# Makita_PSU.net
KiCad netlist of a schematic drawn in EAGLE
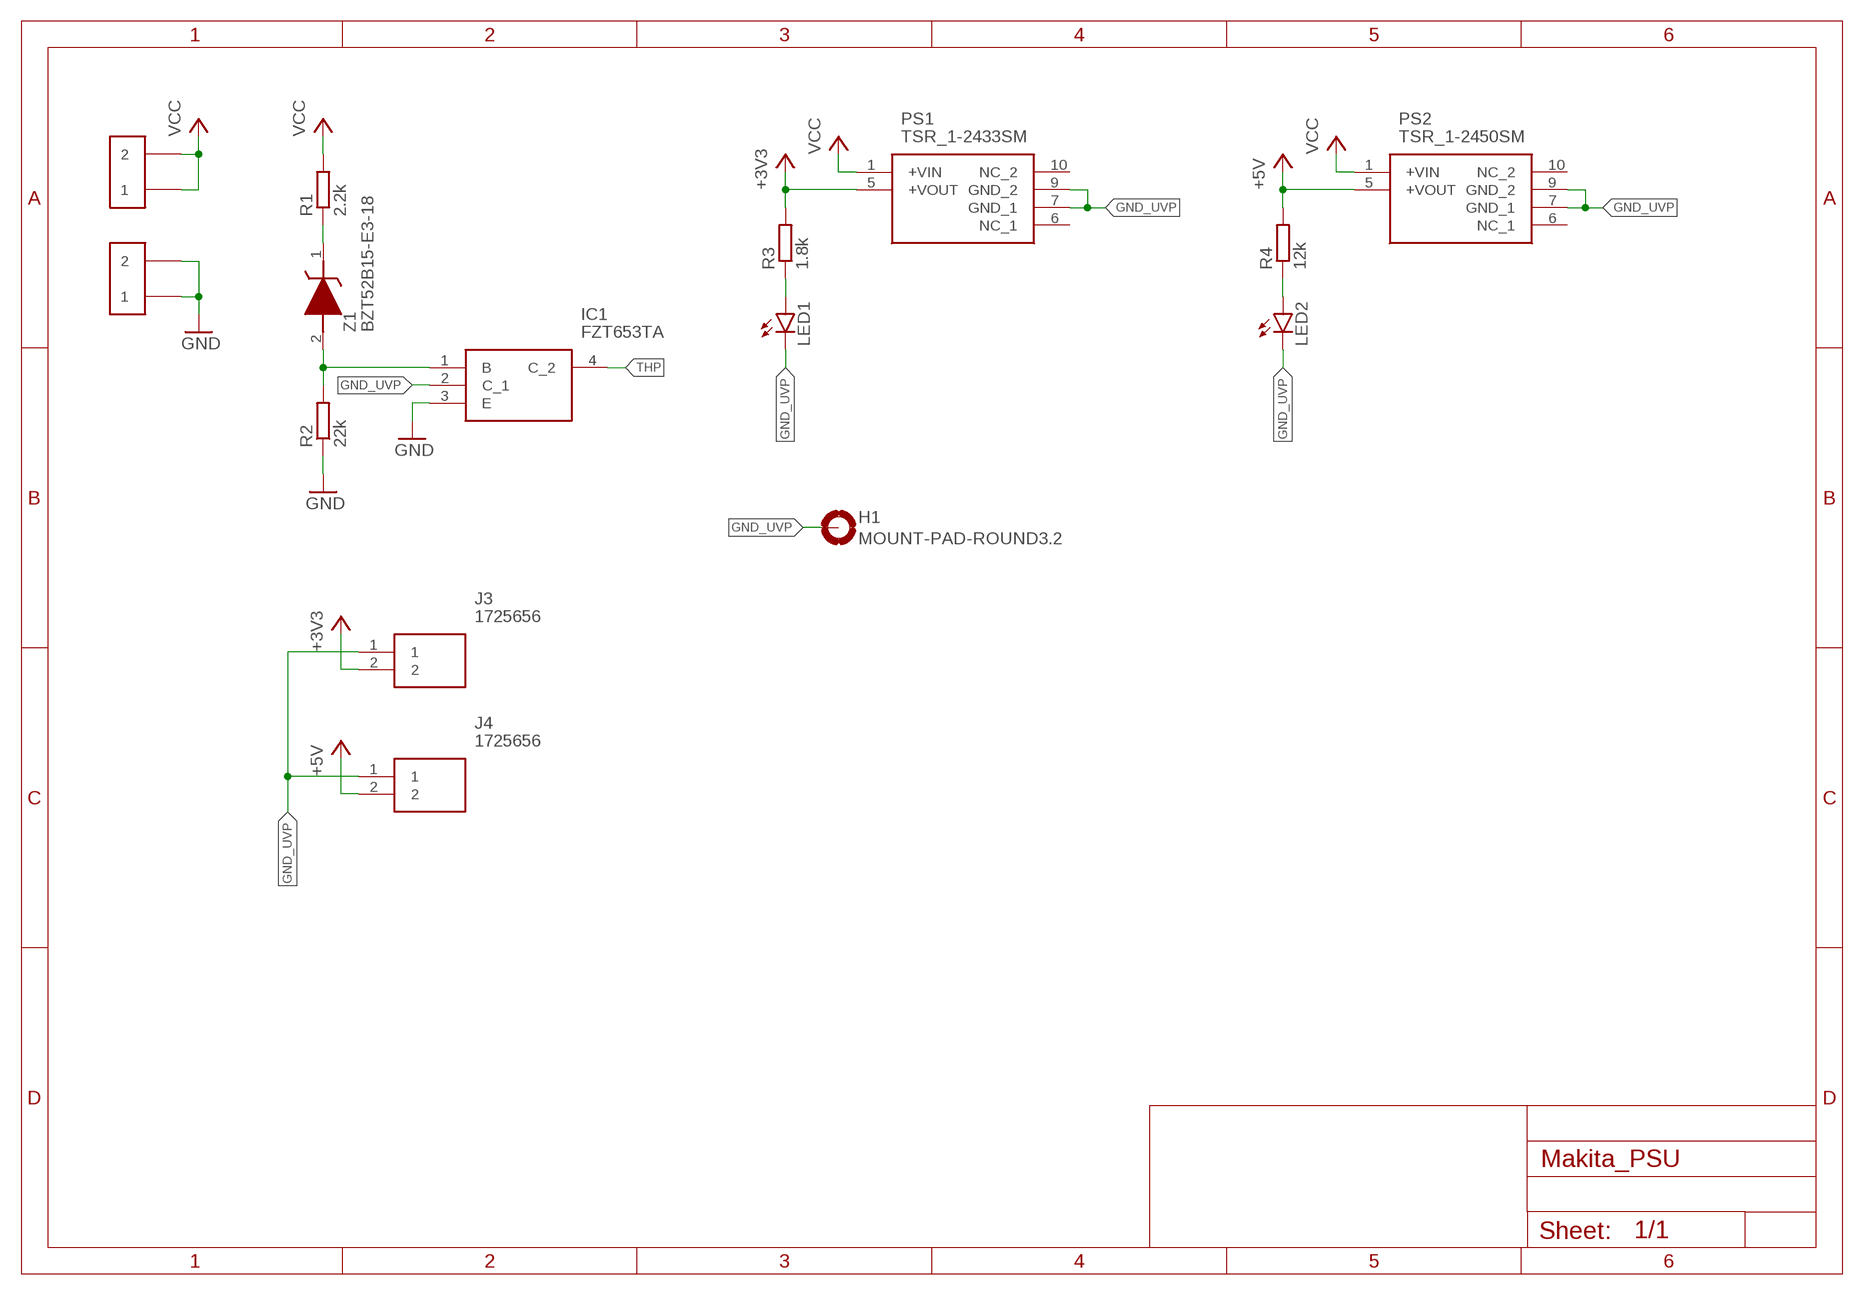
[diagram p0: schematic, sheet 1]

(export (version "E")
  (design (tool "Eeschema 10.0.6"))
  (components
    (comp (ref "H1")
      (value "MOUNT-PAD-ROUND3.2")
      (footprint "eagle-import:3,2-PAD")
      (libsource (lib "eagle-import") (part "MOUNT-PAD-ROUND3.2"))
    )
    (comp (ref "IC1")
      (value "FZT653TA")
      (footprint "eagle-import:SOT230P700X180-4N")
      (fields (field (name "MOUSER_PART_NUMBER") "522-FZT653TA"))
      (libsource (lib "eagle-import") (part "FZT653TA"))
    )
    (comp (ref "J1")
      (value "VOGT_3825Z.68")
      (footprint "eagle-import:VOGT_3825Z.68")
      (libsource (lib "eagle-import") (part "VOGT_3825Z.68"))
    )
    (comp (ref "J2")
      (value "VOGT_3825Z.68")
      (footprint "eagle-import:VOGT_3825Z.68")
      (libsource (lib "eagle-import") (part "VOGT_3825Z.68"))
    )
    (comp (ref "J3")
      (value "1725656")
      (footprint "eagle-import:1725656")
      (fields (field (name "MOUSER_PART_NUMBER") "651-1725656"))
      (libsource (lib "eagle-import") (part "1725656"))
    )
    (comp (ref "J4")
      (value "1725656")
      (footprint "eagle-import:1725656")
      (fields (field (name "MOUSER_PART_NUMBER") "651-1725656"))
      (libsource (lib "eagle-import") (part "1725656"))
    )
    (comp (ref "LED1")
      (value "LEDCHIPLED_0805")
      (footprint "eagle-import:CHIPLED_0805")
      (libsource (lib "eagle-import") (part "LEDCHIPLED_0805"))
    )
    (comp (ref "LED2")
      (value "LEDCHIPLED_0805")
      (footprint "eagle-import:CHIPLED_0805")
      (libsource (lib "eagle-import") (part "LEDCHIPLED_0805"))
    )
    (comp (ref "PS1")
      (value "TSR_1-2433SM")
      (footprint "eagle-import:TSR124120SM")
      (fields
        (field (name "MANUFACTURER_PART_NUMBER") "TSR 1-2433SM")
        (field (name "MOUSER_PART_NUMBER") "495-TSR1-2433SM")
      )
      (libsource (lib "eagle-import") (part "TSR_1-2433SM"))
    )
    (comp (ref "PS2")
      (value "TSR_1-2450SM")
      (footprint "eagle-import:TSR124120SM")
      (fields
        (field (name "MANUFACTURER_PART_NUMBER") "TSR 1-2450SM")
        (field (name "MOUSER_PART_NUMBER") "495-TSR1-2450SM")
      )
      (libsource (lib "eagle-import") (part "TSR_1-2450SM"))
    )
    (comp (ref "R1")
      (value "2.2k")
      (footprint "eagle-import:R0805")
      (libsource (lib "eagle-import") (part "R-EU_R0805"))
    )
    (comp (ref "R2")
      (value "22k")
      (footprint "eagle-import:R0805")
      (libsource (lib "eagle-import") (part "R-EU_R0805"))
    )
    (comp (ref "R3")
      (value "1.8k")
      (footprint "eagle-import:R0805")
      (libsource (lib "eagle-import") (part "R-EU_R0805"))
    )
    (comp (ref "R4")
      (value "12k")
      (footprint "eagle-import:R0805")
      (libsource (lib "eagle-import") (part "R-EU_R0805"))
    )
    (comp (ref "Z1")
      (value "BZT52B15-E3-18")
      (footprint "eagle-import:SOD3716X135N")
      (fields (field (name "MOUSER_PART_NUMBER") "78-BZT52B15-E3-18"))
      (libsource (lib "eagle-import") (part "BZT52B15-E3-18"))
    )
  )
  (nets
    (net (code "1") (name "+3V3") (class "Default")
      (node (ref "J3") (pin "2") (pinfunction "2_2") (pintype "bidirectional"))
      (node (ref "PS1") (pin "5") (pinfunction "+VOUT_5") (pintype "bidirectional"))
      (node (ref "R3") (pin "2") (pinfunction "2_2") (pintype "passive"))
    )
    (net (code "2") (name "+5V") (class "Default")
      (node (ref "J4") (pin "2") (pinfunction "2_2") (pintype "bidirectional"))
      (node (ref "PS2") (pin "5") (pinfunction "+VOUT_5") (pintype "bidirectional"))
      (node (ref "R4") (pin "2") (pinfunction "2_2") (pintype "passive"))
    )
    (net (code "3") (name "GND") (class "Default")
      (node (ref "IC1") (pin "3") (pinfunction "E_3") (pintype "bidirectional"))
      (node (ref "J2") (pin "P$1") (pinfunction "1_P$1") (pintype "bidirectional"))
      (node (ref "J2") (pin "P$2") (pinfunction "2_P$2") (pintype "bidirectional"))
      (node (ref "R2") (pin "1") (pinfunction "1_1") (pintype "passive"))
    )
    (net (code "4") (name "GND_UVP") (class "Default")
      (node (ref "H1") (pin "B3,2") (pinfunction "MOUNT_B3,2") (pintype "passive"))
      (node (ref "IC1") (pin "2") (pinfunction "C_1_2") (pintype "bidirectional"))
      (node (ref "J3") (pin "1") (pinfunction "1_1") (pintype "bidirectional"))
      (node (ref "J4") (pin "1") (pinfunction "1_1") (pintype "bidirectional"))
      (node (ref "LED1") (pin "C") (pinfunction "C_C") (pintype "passive"))
      (node (ref "LED2") (pin "C") (pinfunction "C_C") (pintype "passive"))
      (node (ref "PS1") (pin "7") (pinfunction "GND_1_7") (pintype "bidirectional"))
      (node (ref "PS1") (pin "9") (pinfunction "GND_2_9") (pintype "bidirectional"))
      (node (ref "PS2") (pin "7") (pinfunction "GND_1_7") (pintype "bidirectional"))
      (node (ref "PS2") (pin "9") (pinfunction "GND_2_9") (pintype "bidirectional"))
    )
    (net (code "5") (name "Net-(IC1-B)") (class "Default")
      (node (ref "IC1") (pin "1") (pinfunction "B_1") (pintype "bidirectional"))
      (node (ref "R2") (pin "2") (pinfunction "2_2") (pintype "passive"))
      (node (ref "Z1") (pin "2") (pinfunction "A_2") (pintype "bidirectional"))
    )
    (net (code "6") (name "Net-(LED1-PadA)") (class "Default")
      (node (ref "LED1") (pin "A") (pinfunction "A_A") (pintype "passive"))
      (node (ref "R3") (pin "1") (pinfunction "1_1") (pintype "passive"))
    )
    (net (code "7") (name "Net-(LED2-PadA)") (class "Default")
      (node (ref "LED2") (pin "A") (pinfunction "A_A") (pintype "passive"))
      (node (ref "R4") (pin "1") (pinfunction "1_1") (pintype "passive"))
    )
    (net (code "8") (name "Net-(Z1-K)") (class "Default")
      (node (ref "R1") (pin "1") (pinfunction "1_1") (pintype "passive"))
      (node (ref "Z1") (pin "1") (pinfunction "K_1") (pintype "bidirectional"))
    )
    (net (code "9") (name "THP") (class "Default")
      (node (ref "IC1") (pin "4") (pinfunction "C_2_4") (pintype "bidirectional"))
    )
    (net (code "10") (name "VCC") (class "Default")
      (node (ref "J1") (pin "P$1") (pinfunction "1_P$1") (pintype "bidirectional"))
      (node (ref "J1") (pin "P$2") (pinfunction "2_P$2") (pintype "bidirectional"))
      (node (ref "PS1") (pin "1") (pinfunction "+VIN_1") (pintype "bidirectional"))
      (node (ref "PS2") (pin "1") (pinfunction "+VIN_1") (pintype "bidirectional"))
      (node (ref "R1") (pin "2") (pinfunction "2_2") (pintype "passive"))
    )
    (net (code "11") (name "unconnected-(PS1-NC_1-Pad6)") (class "Default")
      (node (ref "PS1") (pin "6") (pinfunction "NC_1_6") (pintype "bidirectional"))
    )
    (net (code "12") (name "unconnected-(PS1-NC_2-Pad10)") (class "Default")
      (node (ref "PS1") (pin "10") (pinfunction "NC_2_10") (pintype "bidirectional"))
    )
    (net (code "13") (name "unconnected-(PS2-NC_1-Pad6)") (class "Default")
      (node (ref "PS2") (pin "6") (pinfunction "NC_1_6") (pintype "bidirectional"))
    )
    (net (code "14") (name "unconnected-(PS2-NC_2-Pad10)") (class "Default")
      (node (ref "PS2") (pin "10") (pinfunction "NC_2_10") (pintype "bidirectional"))
    )
  )
)
